# design.net
KiCad netlist of a schematic drawn in Altium Designer
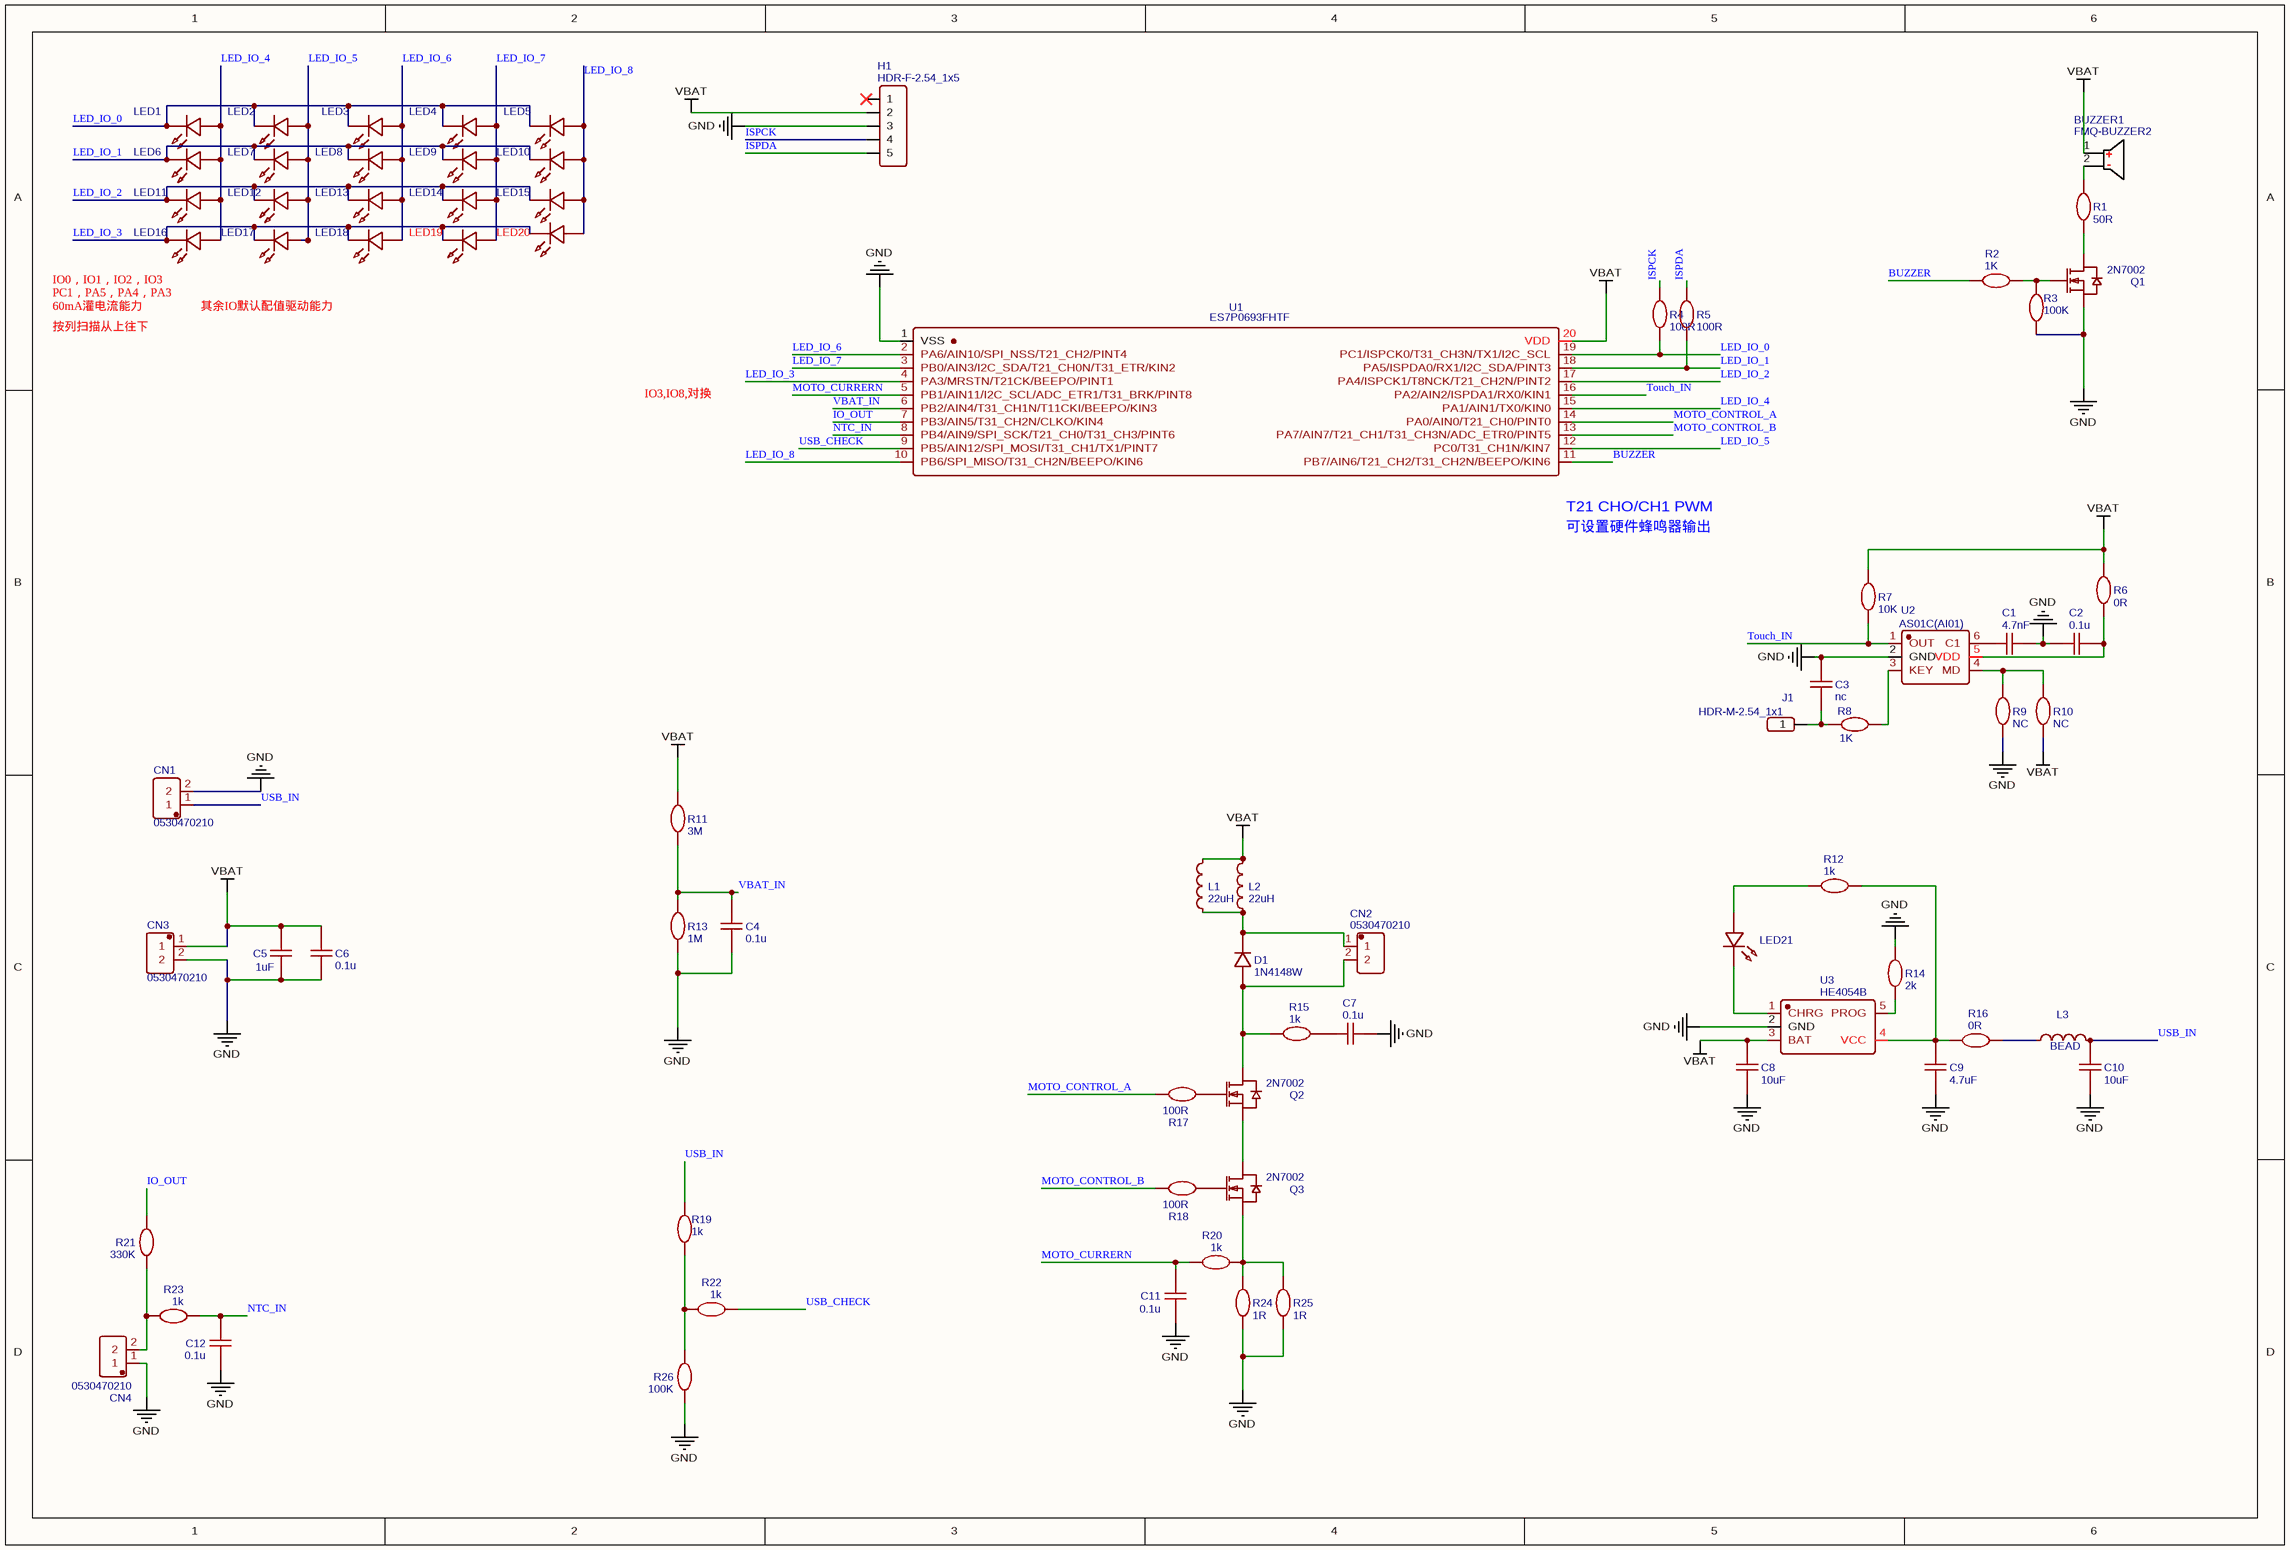
[diagram p0: 搅拌杯原理图.schdoc]

(export (version "E")
  (design (tool "Eeschema 10.0.6"))
  (components
    (comp (ref "BUZZER1")
      (value "FMQ-BUZZER2")
      (footprint "BUZ-TH_BD12.0-P7.60-D0.6-FD")
      (fields (field (name "BOM_SUPPLIER PART") "C9900006103") (field (name "CONTRIBUTOR") "LCSC"))
      (libsource (lib "altium-import") (part "root_0_FMQ-BUZZER2_"))
    )
    (comp (ref "C1")
      (value "4.7nF")
      (footprint "C0603")
      (fields (field (name "CONTRIBUTOR") "LCEDA_Lib"))
      (libsource (lib "altium-import") (part "root_0_4.7nF_"))
    )
    (comp (ref "C2")
      (value "0.1u")
      (footprint "C0603")
      (fields (field (name "CONTRIBUTOR") "LCEDA_Lib"))
      (libsource (lib "altium-import") (part "root_0_0.1u_"))
    )
    (comp (ref "C3")
      (value "nc")
      (footprint "C0603")
      (fields (field (name "CONTRIBUTOR") "LCEDA_Lib"))
      (libsource (lib "altium-import") (part "root_1_nc_"))
    )
    (comp (ref "C4")
      (value "0.1u")
      (footprint "C0603")
      (fields (field (name "CONTRIBUTOR") "LCEDA_Lib"))
      (libsource (lib "altium-import") (part "root_1_0.1u_"))
    )
    (comp (ref "C5")
      (value "1uF")
      (footprint "C0603")
      (fields (field (name "CONTRIBUTOR") "LCEDA_Lib"))
      (libsource (lib "altium-import") (part "root_3_1uF_"))
    )
    (comp (ref "C6")
      (value "0.1u")
      (footprint "C0603")
      (fields (field (name "CONTRIBUTOR") "LCEDA_Lib"))
      (libsource (lib "altium-import") (part "root_3_0.1u_"))
    )
    (comp (ref "C7")
      (value "0.1u")
      (footprint "C0603")
      (fields (field (name "CONTRIBUTOR") "LCEDA_Lib"))
      (libsource (lib "altium-import") (part "root_2_0.1u_"))
    )
    (comp (ref "C8")
      (value "10uF")
      (footprint "C0603")
      (fields (field (name "CONTRIBUTOR") "LCEDA_Lib"))
      (libsource (lib "altium-import") (part "root_1_10uF_"))
    )
    (comp (ref "C9")
      (value "4.7uF")
      (footprint "C0603")
      (fields (field (name "CONTRIBUTOR") "LCEDA_Lib"))
      (libsource (lib "altium-import") (part "root_1_4.7uF_"))
    )
    (comp (ref "C10")
      (value "10uF")
      (footprint "C0603")
      (fields (field (name "CONTRIBUTOR") "LCEDA_Lib"))
      (libsource (lib "altium-import") (part "root_1_10uF_"))
    )
    (comp (ref "C11")
      (value "0.1u")
      (footprint "C0603")
      (fields (field (name "CONTRIBUTOR") "LCEDA_Lib"))
      (libsource (lib "") (part "root_1_0.1u__1"))
    )
    (comp (ref "C12")
      (value "0.1u")
      (footprint "C0603")
      (fields (field (name "CONTRIBUTOR") "LCEDA_Lib"))
      (libsource (lib "") (part "root_3_0.1u__1"))
    )
    (comp (ref "CN1")
      (value "0530470210")
      (footprint "CONN-TH_0530470210")
      (fields (field (name "BOM_SUPPLIER PART") "C114130") (field (name "CONTRIBUTOR") "LCSC"))
      (libsource (lib "") (part "root_0_mirrored_0530470210__1"))
    )
    (comp (ref "CN2")
      (value "0530470210")
      (footprint "CONN-TH_0530470210")
      (fields (field (name "BOM_SUPPLIER PART") "C114130") (field (name "CONTRIBUTOR") "LCSC"))
      (libsource (lib "altium-import") (part "root_0_0530470210_"))
    )
    (comp (ref "CN3")
      (value "0530470210")
      (footprint "CONN-TH_0530470210")
      (fields (field (name "BOM_SUPPLIER PART") "C114130") (field (name "CONTRIBUTOR") "LCSC"))
      (libsource (lib "altium-import") (part "root_0_mirrored_0530470210_"))
    )
    (comp (ref "CN4")
      (value "0530470210")
      (footprint "CONN-TH_0530470210")
      (fields (field (name "BOM_SUPPLIER PART") "C114130") (field (name "CONTRIBUTOR") "LCSC"))
      (libsource (lib "") (part "root_0_0530470210__1"))
    )
    (comp (ref "D1")
      (value "1N4148W")
      (footprint "SOD-123FL_L2.6-W1.6-LS3.4-RD")
      (fields (field (name "BOM_SUPPLIER PART") "C129216") (field (name "CONTRIBUTOR") "LCEDA_Lib"))
      (libsource (lib "altium-import") (part "root_1_1N4148W_"))
    )
    (comp (ref "H1")
      (value "HDR-F-2.54_1x5")
      (footprint "1.27mm_5PIN")
      (fields (field (name "BOM_SUPPLIER PART") "C50950") (field (name "CONTRIBUTOR") "LCEDA_Lib"))
      (libsource (lib "altium-import") (part "root_0_HDR-F-2.54_1x5_"))
    )
    (comp (ref "J1")
      (value "HDR-M-2.54_1x1")
      (footprint "HDR-M-2.54_1X1")
      (fields (field (name "BOM_SUPPLIER PART") "C81276") (field (name "CONTRIBUTOR") "LCEDA_Lib"))
      (libsource (lib "altium-import") (part "root_2_HDR-M-2.54_1x1_"))
    )
    (comp (ref "L1")
      (value "22uH")
      (footprint "L0603")
      (fields (field (name "CONTRIBUTOR") "LCEDA_Lib"))
      (libsource (lib "altium-import") (part "root_1_22uH_"))
    )
    (comp (ref "L2")
      (value "22uH")
      (footprint "L0603")
      (fields (field (name "CONTRIBUTOR") "LCEDA_Lib"))
      (libsource (lib "altium-import") (part "root_1_22uH_"))
    )
    (comp (ref "L3")
      (value "BEAD")
      (footprint "L0603")
      (fields (field (name "CONTRIBUTOR") "LCEDA_Lib"))
      (libsource (lib "altium-import") (part "root_0_22uH_"))
    )
    (comp (ref "LED1")
      (value "LED-0603_W")
      (footprint "LED0603-FD_WHITE")
      (fields
        (field (name "BOM_MANUFACTURER PART") "17-21SURC/S530-A3/TR8")
        (field (name "BOM_SUPPLIER PART") "C72037")
        (field (name "CONTRIBUTOR") "LCEDA_Lib")
      )
      (libsource (lib "altium-import") (part "root_2_LED-0603_W_"))
    )
    (comp (ref "LED2")
      (value "LED-0603_W")
      (footprint "LED0603-FD_WHITE")
      (fields
        (field (name "BOM_MANUFACTURER PART") "17-21SURC/S530-A3/TR8")
        (field (name "BOM_SUPPLIER PART") "C72037")
        (field (name "CONTRIBUTOR") "LCEDA_Lib")
      )
      (libsource (lib "altium-import") (part "root_2_LED-0603_W_"))
    )
    (comp (ref "LED3")
      (value "LED-0603_W")
      (footprint "LED0603-FD_WHITE")
      (fields
        (field (name "BOM_MANUFACTURER PART") "17-21SURC/S530-A3/TR8")
        (field (name "BOM_SUPPLIER PART") "C72037")
        (field (name "CONTRIBUTOR") "LCEDA_Lib")
      )
      (libsource (lib "altium-import") (part "root_2_LED-0603_W_"))
    )
    (comp (ref "LED4")
      (value "LED-0603_W")
      (footprint "LED0603-FD_WHITE")
      (fields
        (field (name "BOM_MANUFACTURER PART") "17-21SURC/S530-A3/TR8")
        (field (name "BOM_SUPPLIER PART") "C72037")
        (field (name "CONTRIBUTOR") "LCEDA_Lib")
      )
      (libsource (lib "altium-import") (part "root_2_LED-0603_W_"))
    )
    (comp (ref "LED5")
      (value "LED-0603_W")
      (footprint "LED0603-FD_WHITE")
      (fields
        (field (name "BOM_MANUFACTURER PART") "17-21SURC/S530-A3/TR8")
        (field (name "BOM_SUPPLIER PART") "C72037")
        (field (name "CONTRIBUTOR") "LCEDA_Lib")
      )
      (libsource (lib "altium-import") (part "root_2_LED-0603_W_"))
    )
    (comp (ref "LED6")
      (value "LED-0603_W")
      (footprint "LED0603-FD_WHITE")
      (fields
        (field (name "BOM_MANUFACTURER PART") "17-21SURC/S530-A3/TR8")
        (field (name "BOM_SUPPLIER PART") "C72037")
        (field (name "CONTRIBUTOR") "LCEDA_Lib")
      )
      (libsource (lib "altium-import") (part "root_2_LED-0603_W_"))
    )
    (comp (ref "LED7")
      (value "LED-0603_W")
      (footprint "LED0603-FD_WHITE")
      (fields
        (field (name "BOM_MANUFACTURER PART") "17-21SURC/S530-A3/TR8")
        (field (name "BOM_SUPPLIER PART") "C72037")
        (field (name "CONTRIBUTOR") "LCEDA_Lib")
      )
      (libsource (lib "altium-import") (part "root_2_LED-0603_W_"))
    )
    (comp (ref "LED8")
      (value "LED-0603_W")
      (footprint "LED0603-FD_WHITE")
      (fields
        (field (name "BOM_MANUFACTURER PART") "17-21SURC/S530-A3/TR8")
        (field (name "BOM_SUPPLIER PART") "C72037")
        (field (name "CONTRIBUTOR") "LCEDA_Lib")
      )
      (libsource (lib "altium-import") (part "root_2_LED-0603_W_"))
    )
    (comp (ref "LED9")
      (value "LED-0603_W")
      (footprint "LED0603-FD_WHITE")
      (fields
        (field (name "BOM_MANUFACTURER PART") "17-21SURC/S530-A3/TR8")
        (field (name "BOM_SUPPLIER PART") "C72037")
        (field (name "CONTRIBUTOR") "LCEDA_Lib")
      )
      (libsource (lib "altium-import") (part "root_2_LED-0603_W_"))
    )
    (comp (ref "LED10")
      (value "LED-0603_W")
      (footprint "LED0603-FD_WHITE")
      (fields
        (field (name "BOM_MANUFACTURER PART") "17-21SURC/S530-A3/TR8")
        (field (name "BOM_SUPPLIER PART") "C72037")
        (field (name "CONTRIBUTOR") "LCEDA_Lib")
      )
      (libsource (lib "altium-import") (part "root_2_LED-0603_W_"))
    )
    (comp (ref "LED11")
      (value "LED-0603_W")
      (footprint "LED0603-FD_WHITE")
      (fields
        (field (name "BOM_MANUFACTURER PART") "17-21SURC/S530-A3/TR8")
        (field (name "BOM_SUPPLIER PART") "C72037")
        (field (name "CONTRIBUTOR") "LCEDA_Lib")
      )
      (libsource (lib "altium-import") (part "root_2_LED-0603_W_"))
    )
    (comp (ref "LED12")
      (value "LED-0603_W")
      (footprint "LED0603-FD_WHITE")
      (fields
        (field (name "BOM_MANUFACTURER PART") "17-21SURC/S530-A3/TR8")
        (field (name "BOM_SUPPLIER PART") "C72037")
        (field (name "CONTRIBUTOR") "LCEDA_Lib")
      )
      (libsource (lib "altium-import") (part "root_2_LED-0603_W_"))
    )
    (comp (ref "LED13")
      (value "LED-0603_W")
      (footprint "LED0603-FD_WHITE")
      (fields
        (field (name "BOM_MANUFACTURER PART") "17-21SURC/S530-A3/TR8")
        (field (name "BOM_SUPPLIER PART") "C72037")
        (field (name "CONTRIBUTOR") "LCEDA_Lib")
      )
      (libsource (lib "altium-import") (part "root_2_LED-0603_W_"))
    )
    (comp (ref "LED14")
      (value "LED-0603_W")
      (footprint "LED0603-FD_WHITE")
      (fields
        (field (name "BOM_MANUFACTURER PART") "17-21SURC/S530-A3/TR8")
        (field (name "BOM_SUPPLIER PART") "C72037")
        (field (name "CONTRIBUTOR") "LCEDA_Lib")
      )
      (libsource (lib "altium-import") (part "root_2_LED-0603_W_"))
    )
    (comp (ref "LED15")
      (value "LED-0603_W")
      (footprint "LED0603-FD_WHITE")
      (fields
        (field (name "BOM_MANUFACTURER PART") "17-21SURC/S530-A3/TR8")
        (field (name "BOM_SUPPLIER PART") "C72037")
        (field (name "CONTRIBUTOR") "LCEDA_Lib")
      )
      (libsource (lib "altium-import") (part "root_2_LED-0603_W_"))
    )
    (comp (ref "LED16")
      (value "LED-0603_W")
      (footprint "LED0603-FD_WHITE")
      (fields
        (field (name "BOM_MANUFACTURER PART") "17-21SURC/S530-A3/TR8")
        (field (name "BOM_SUPPLIER PART") "C72037")
        (field (name "CONTRIBUTOR") "LCEDA_Lib")
      )
      (libsource (lib "altium-import") (part "root_2_LED-0603_W_"))
    )
    (comp (ref "LED17")
      (value "LED-0603_W")
      (footprint "LED0603-FD_WHITE")
      (fields
        (field (name "BOM_MANUFACTURER PART") "17-21SURC/S530-A3/TR8")
        (field (name "BOM_SUPPLIER PART") "C72037")
        (field (name "CONTRIBUTOR") "LCEDA_Lib")
      )
      (libsource (lib "altium-import") (part "root_2_LED-0603_W_"))
    )
    (comp (ref "LED18")
      (value "LED-0603_W")
      (footprint "LED0603-FD_WHITE")
      (fields
        (field (name "BOM_MANUFACTURER PART") "17-21SURC/S530-A3/TR8")
        (field (name "BOM_SUPPLIER PART") "C72037")
        (field (name "CONTRIBUTOR") "LCEDA_Lib")
      )
      (libsource (lib "altium-import") (part "root_2_LED-0603_W_"))
    )
    (comp (ref "LED19")
      (value "LED-0603_W")
      (footprint "LED0603-FD_WHITE")
      (fields
        (field (name "BOM_MANUFACTURER PART") "17-21SURC/S530-A3/TR8")
        (field (name "BOM_SUPPLIER PART") "C72037")
        (field (name "CONTRIBUTOR") "LCEDA_Lib")
      )
      (libsource (lib "altium-import") (part "root_2_LED-0603_W_"))
    )
    (comp (ref "LED20")
      (value "LED-0603_W")
      (footprint "LED0603-FD_WHITE")
      (fields
        (field (name "BOM_MANUFACTURER PART") "17-21SURC/S530-A3/TR8")
        (field (name "BOM_SUPPLIER PART") "C72037")
        (field (name "CONTRIBUTOR") "LCEDA_Lib")
      )
      (libsource (lib "altium-import") (part "root_2_LED-0603_W_"))
    )
    (comp (ref "LED21")
      (value "LED-0603_W")
      (footprint "LED0603-FD_WHITE")
      (fields
        (field (name "BOM_MANUFACTURER PART") "17-21SURC/S530-A3/TR8")
        (field (name "BOM_SUPPLIER PART") "C72037")
        (field (name "CONTRIBUTOR") "LCEDA_Lib")
      )
      (libsource (lib "altium-import") (part "root_3_LED-0603_W_"))
    )
    (comp (ref "Q1")
      (value "2N7002")
      (footprint "SOT-23_L2.9-W1.3-P0.95-LS2.4-BR")
      (fields
        (field (name "BOM_MANUFACTURER PART") "2N7002,215")
        (field (name "BOM_SUPPLIER PART") "C65189")
        (field (name "CONTRIBUTOR") "LCEDA_Lib")
      )
      (libsource (lib "altium-import") (part "root_2_2N7002_"))
    )
    (comp (ref "Q2")
      (value "2N7002")
      (footprint "SOT-23_L2.9-W1.3-P0.95-LS2.4-BR")
      (fields
        (field (name "BOM_MANUFACTURER PART") "2N7002,215")
        (field (name "BOM_SUPPLIER PART") "C65189")
        (field (name "CONTRIBUTOR") "LCEDA_Lib")
      )
      (libsource (lib "altium-import") (part "root_2_2N7002_"))
    )
    (comp (ref "Q3")
      (value "2N7002")
      (footprint "SOT-23_L2.9-W1.3-P0.95-LS2.4-BR")
      (fields
        (field (name "BOM_MANUFACTURER PART") "2N7002,215")
        (field (name "BOM_SUPPLIER PART") "C65189")
        (field (name "CONTRIBUTOR") "LCEDA_Lib")
      )
      (libsource (lib "altium-import") (part "root_2_2N7002_"))
    )
    (comp (ref "R1")
      (value "50R")
      (footprint "R0603")
      (fields (field (name "CONTRIBUTOR") "LCEDA_Lib"))
      (libsource (lib "altium-import") (part "root_3_100R_"))
    )
    (comp (ref "R2")
      (value "1K")
      (footprint "R0603")
      (fields (field (name "CONTRIBUTOR") "LCEDA_Lib"))
      (libsource (lib "altium-import") (part "root_2_1K_"))
    )
    (comp (ref "R3")
      (value "100K")
      (footprint "R0603")
      (fields (field (name "CONTRIBUTOR") "LCEDA_Lib"))
      (libsource (lib "altium-import") (part "root_3_1K_"))
    )
    (comp (ref "R4")
      (value "100R")
      (footprint "R0603")
      (fields (field (name "CONTRIBUTOR") "LCEDA_Lib"))
      (libsource (lib "altium-import") (part "root_3_100R_"))
    )
    (comp (ref "R5")
      (value "100R")
      (footprint "R0603")
      (fields (field (name "CONTRIBUTOR") "LCEDA_Lib"))
      (libsource (lib "altium-import") (part "root_3_100R_"))
    )
    (comp (ref "R6")
      (value "0R")
      (footprint "R0603")
      (fields (field (name "CONTRIBUTOR") "LCEDA_Lib"))
      (libsource (lib "altium-import") (part "root_1_NC_"))
    )
    (comp (ref "R7")
      (value "10K")
      (footprint "R0603")
      (fields (field (name "CONTRIBUTOR") "LCEDA_Lib"))
      (libsource (lib "altium-import") (part "root_1_NC_"))
    )
    (comp (ref "R8")
      (value "1K")
      (footprint "R0603")
      (fields (field (name "CONTRIBUTOR") "LCEDA_Lib"))
      (libsource (lib "altium-import") (part "root_2_1K_"))
    )
    (comp (ref "R9")
      (value "NC")
      (footprint "R0603")
      (fields (field (name "CONTRIBUTOR") "LCEDA_Lib"))
      (libsource (lib "altium-import") (part "root_1_NC_"))
    )
    (comp (ref "R10")
      (value "NC")
      (footprint "R0603")
      (fields (field (name "CONTRIBUTOR") "LCEDA_Lib"))
      (libsource (lib "altium-import") (part "root_1_NC_"))
    )
    (comp (ref "R11")
      (value "3M")
      (footprint "R0603")
      (fields (field (name "CONTRIBUTOR") "LCEDA_Lib"))
      (libsource (lib "altium-import") (part "root_1_430k_"))
    )
    (comp (ref "R12")
      (value "1k")
      (footprint "R0603")
      (fields (field (name "CONTRIBUTOR") "LCEDA_Lib"))
      (libsource (lib "") (part "root_2_1k__1"))
    )
    (comp (ref "R13")
      (value "1M")
      (footprint "R0603")
      (fields (field (name "CONTRIBUTOR") "LCEDA_Lib"))
      (libsource (lib "altium-import") (part "root_1_430K_"))
    )
    (comp (ref "R14")
      (value "2k")
      (footprint "R0603")
      (fields (field (name "CONTRIBUTOR") "LCEDA_Lib"))
      (libsource (lib "altium-import") (part "root_1_1k_"))
    )
    (comp (ref "R15")
      (value "1k")
      (footprint "R0603")
      (fields (field (name "CONTRIBUTOR") "LCEDA_Lib"))
      (libsource (lib "") (part "root_2_1k__1"))
    )
    (comp (ref "R16")
      (value "0R")
      (footprint "R0603")
      (fields (field (name "CONTRIBUTOR") "LCEDA_Lib"))
      (libsource (lib "altium-import") (part "root_0_NC_"))
    )
    (comp (ref "R17")
      (value "100R")
      (footprint "R0603")
      (fields (field (name "CONTRIBUTOR") "LCEDA_Lib"))
      (libsource (lib "altium-import") (part "root_2_100R_"))
    )
    (comp (ref "R18")
      (value "100R")
      (footprint "R0603")
      (fields (field (name "CONTRIBUTOR") "LCEDA_Lib"))
      (libsource (lib "altium-import") (part "root_2_100R_"))
    )
    (comp (ref "R19")
      (value "1k")
      (footprint "R0603")
      (fields (field (name "CONTRIBUTOR") "LCEDA_Lib"))
      (libsource (lib "altium-import") (part "root_3_1k_"))
    )
    (comp (ref "R20")
      (value "1k")
      (footprint "R0603")
      (fields (field (name "CONTRIBUTOR") "LCEDA_Lib"))
      (libsource (lib "altium-import") (part "root_0_1k_"))
    )
    (comp (ref "R21")
      (value "330K")
      (footprint "R0603")
      (fields (field (name "CONTRIBUTOR") "LCEDA_Lib"))
      (libsource (lib "altium-import") (part "root_3_33K_"))
    )
    (comp (ref "R22")
      (value "1k")
      (footprint "R0603")
      (fields (field (name "CONTRIBUTOR") "LCEDA_Lib"))
      (libsource (lib "altium-import") (part "root_2_1k_"))
    )
    (comp (ref "R23")
      (value "1k")
      (footprint "R0603")
      (fields (field (name "CONTRIBUTOR") "LCEDA_Lib"))
      (libsource (lib "altium-import") (part "root_2_1k_"))
    )
    (comp (ref "R24")
      (value "1R")
      (footprint "R1206")
      (fields (field (name "CONTRIBUTOR") "LCEDA_Lib"))
      (libsource (lib "altium-import") (part "root_1_1R_"))
    )
    (comp (ref "R25")
      (value "1R")
      (footprint "R1206")
      (fields (field (name "CONTRIBUTOR") "LCEDA_Lib"))
      (libsource (lib "altium-import") (part "root_1_1R_"))
    )
    (comp (ref "R26")
      (value "100K")
      (footprint "R0603")
      (fields (field (name "CONTRIBUTOR") "LCEDA_Lib"))
      (libsource (lib "altium-import") (part "root_3_33K_"))
    )
    (comp (ref "U1")
      (value "ES7P0693FHTF")
      (footprint "TSOP20")
      (fields (field (name "CONTRIBUTOR") "zime_zl"))
      (libsource (lib "altium-import") (part "root_0_ES7P0693FHTF_"))
    )
    (comp (ref "U2")
      (value "AS01C(AI01)")
      (footprint "SOT-23-6_L2.9-W1.6-P0.95-LS2.8-BL")
      (fields (field (name "BOM_SUPPLIER PART") "C389617") (field (name "CONTRIBUTOR") "LCSC"))
      (libsource (lib "altium-import") (part "root_0_AS01C(AI01)_"))
    )
    (comp (ref "U3")
      (value "HE4054B")
      (footprint "SOT-23-5_L3.0-W1.7-P0.95-LS2.8-BR")
      (fields (field (name "BOM_SUPPLIER PART") "C711953") (field (name "CONTRIBUTOR") "LCSC"))
      (libsource (lib "altium-import") (part "root_0_HE4054B_"))
    )
  )
  (nets
    (net (code "1") (name "/BUZZER") (class "Default")
      (node (ref "R2") (pin "2") (pinfunction "2_2") (pintype "passive"))
      (node (ref "U1") (pin "11") (pinfunction "PB7/AIN6/T21_CH2/T31_CH2N/BEEPO/KIN6_11") (pintype "passive"))
    )
    (net (code "2") (name "/IO_OUT") (class "Default")
      (node (ref "R21") (pin "1") (pinfunction "1_1") (pintype "passive"))
      (node (ref "U1") (pin "7") (pinfunction "PB3/AIN5/T31_CH2N/CLKO/KIN4_7") (pintype "passive"))
    )
    (net (code "3") (name "/ISPCK") (class "Default")
      (node (ref "H1") (pin "4") (pinfunction "4_4") (pintype "passive"))
      (node (ref "R4") (pin "1") (pinfunction "1_1") (pintype "passive"))
    )
    (net (code "4") (name "/ISPDA") (class "Default")
      (node (ref "H1") (pin "5") (pinfunction "5_5") (pintype "passive"))
      (node (ref "R5") (pin "1") (pinfunction "1_1") (pintype "passive"))
    )
    (net (code "5") (name "/LED_IO_0") (class "Default")
      (node (ref "LED1") (pin "2") (pinfunction "2_2") (pintype "passive"))
      (node (ref "LED2") (pin "2") (pinfunction "2_2") (pintype "passive"))
      (node (ref "LED3") (pin "2") (pinfunction "2_2") (pintype "passive"))
      (node (ref "LED4") (pin "2") (pinfunction "2_2") (pintype "passive"))
      (node (ref "LED5") (pin "2") (pinfunction "2_2") (pintype "passive"))
      (node (ref "R4") (pin "2") (pinfunction "2_2") (pintype "passive"))
      (node (ref "U1") (pin "19") (pinfunction "PC1/ISPCK0/T31_CH3N/TX1/I2C_SCL_19") (pintype "passive"))
    )
    (net (code "6") (name "/LED_IO_1") (class "Default")
      (node (ref "LED10") (pin "2") (pinfunction "2_2") (pintype "passive"))
      (node (ref "LED6") (pin "2") (pinfunction "2_2") (pintype "passive"))
      (node (ref "LED7") (pin "2") (pinfunction "2_2") (pintype "passive"))
      (node (ref "LED8") (pin "2") (pinfunction "2_2") (pintype "passive"))
      (node (ref "LED9") (pin "2") (pinfunction "2_2") (pintype "passive"))
      (node (ref "R5") (pin "2") (pinfunction "2_2") (pintype "passive"))
      (node (ref "U1") (pin "18") (pinfunction "PA5/ISPDA0/RX1/I2C_SDA/PINT3_18") (pintype "passive"))
    )
    (net (code "7") (name "/LED_IO_2") (class "Default")
      (node (ref "LED11") (pin "2") (pinfunction "2_2") (pintype "passive"))
      (node (ref "LED12") (pin "2") (pinfunction "2_2") (pintype "passive"))
      (node (ref "LED13") (pin "2") (pinfunction "2_2") (pintype "passive"))
      (node (ref "LED14") (pin "2") (pinfunction "2_2") (pintype "passive"))
      (node (ref "LED15") (pin "2") (pinfunction "2_2") (pintype "passive"))
      (node (ref "U1") (pin "17") (pinfunction "PA4/ISPCK1/T8NCK/T21_CH2N/PINT2_17") (pintype "passive"))
    )
    (net (code "8") (name "/LED_IO_3") (class "Default")
      (node (ref "LED16") (pin "2") (pinfunction "2_2") (pintype "passive"))
      (node (ref "LED17") (pin "2") (pinfunction "2_2") (pintype "passive"))
      (node (ref "LED18") (pin "2") (pinfunction "2_2") (pintype "passive"))
      (node (ref "LED19") (pin "2") (pinfunction "2_2") (pintype "passive"))
      (node (ref "LED20") (pin "2") (pinfunction "2_2") (pintype "passive"))
      (node (ref "U1") (pin "4") (pinfunction "PA3/MRSTN/T21CK/BEEPO/PINT1_4") (pintype "passive"))
    )
    (net (code "9") (name "/LED_IO_4") (class "Default")
      (node (ref "LED1") (pin "1") (pinfunction "1_1") (pintype "passive"))
      (node (ref "LED11") (pin "1") (pinfunction "1_1") (pintype "passive"))
      (node (ref "LED16") (pin "1") (pinfunction "1_1") (pintype "passive"))
      (node (ref "LED6") (pin "1") (pinfunction "1_1") (pintype "passive"))
      (node (ref "U1") (pin "15") (pinfunction "PA1/AIN1/TX0/KIN0_15") (pintype "passive"))
    )
    (net (code "10") (name "/LED_IO_5") (class "Default")
      (node (ref "LED12") (pin "1") (pinfunction "1_1") (pintype "passive"))
      (node (ref "LED17") (pin "1") (pinfunction "1_1") (pintype "passive"))
      (node (ref "LED2") (pin "1") (pinfunction "1_1") (pintype "passive"))
      (node (ref "LED7") (pin "1") (pinfunction "1_1") (pintype "passive"))
      (node (ref "U1") (pin "12") (pinfunction "PC0/T31_CH1N/KIN7_12") (pintype "passive"))
    )
    (net (code "11") (name "/LED_IO_6") (class "Default")
      (node (ref "LED13") (pin "1") (pinfunction "1_1") (pintype "passive"))
      (node (ref "LED18") (pin "1") (pinfunction "1_1") (pintype "passive"))
      (node (ref "LED3") (pin "1") (pinfunction "1_1") (pintype "passive"))
      (node (ref "LED8") (pin "1") (pinfunction "1_1") (pintype "passive"))
      (node (ref "U1") (pin "2") (pinfunction "PA6/AIN10/SPI_NSS/T21_CH2/PINT4_2") (pintype "passive"))
    )
    (net (code "12") (name "/LED_IO_7") (class "Default")
      (node (ref "LED14") (pin "1") (pinfunction "1_1") (pintype "passive"))
      (node (ref "LED19") (pin "1") (pinfunction "1_1") (pintype "passive"))
      (node (ref "LED4") (pin "1") (pinfunction "1_1") (pintype "passive"))
      (node (ref "LED9") (pin "1") (pinfunction "1_1") (pintype "passive"))
      (node (ref "U1") (pin "3") (pinfunction "PB0/AIN3/I2C_SDA/T21_CH0N/T31_ETR/KIN2_3") (pintype "passive"))
    )
    (net (code "13") (name "/LED_IO_8") (class "Default")
      (node (ref "LED10") (pin "1") (pinfunction "1_1") (pintype "passive"))
      (node (ref "LED15") (pin "1") (pinfunction "1_1") (pintype "passive"))
      (node (ref "LED20") (pin "1") (pinfunction "1_1") (pintype "passive"))
      (node (ref "LED5") (pin "1") (pinfunction "1_1") (pintype "passive"))
      (node (ref "U1") (pin "10") (pinfunction "PB6/SPI_MISO/T31_CH2N/BEEPO/KIN6_10") (pintype "passive"))
    )
    (net (code "14") (name "/MOTO_CONTROL_A") (class "Default")
      (node (ref "R17") (pin "1") (pinfunction "1_1") (pintype "passive"))
      (node (ref "U1") (pin "14") (pinfunction "PA0/AIN0/T21_CH0/PINT0_14") (pintype "passive"))
    )
    (net (code "15") (name "/MOTO_CONTROL_B") (class "Default")
      (node (ref "R18") (pin "1") (pinfunction "1_1") (pintype "passive"))
      (node (ref "U1") (pin "13") (pinfunction "PA7/AIN7/T21_CH1/T31_CH3N/ADC_ETR0/PINT5_13") (pintype "passive"))
    )
    (net (code "16") (name "/MOTO_CURRERN") (class "Default")
      (node (ref "C11") (pin "2") (pinfunction "2_2") (pintype "passive"))
      (node (ref "R20") (pin "2") (pinfunction "2_2") (pintype "passive"))
      (node (ref "U1") (pin "5") (pinfunction "PB1/AIN11/I2C_SCL/ADC_ETR1/T31_BRK/PINT8_5") (pintype "passive"))
    )
    (net (code "17") (name "/NTC_IN") (class "Default")
      (node (ref "C12") (pin "1") (pinfunction "1_1") (pintype "passive"))
      (node (ref "R23") (pin "2") (pinfunction "2_2") (pintype "passive"))
      (node (ref "U1") (pin "8") (pinfunction "PB4/AIN9/SPI_SCK/T21_CH0/T31_CH3/PINT6_8") (pintype "passive"))
    )
    (net (code "18") (name "/Touch_IN") (class "Default")
      (node (ref "R7") (pin "1") (pinfunction "1_1") (pintype "passive"))
      (node (ref "U1") (pin "16") (pinfunction "PA2/AIN2/ISPDA1/RX0/KIN1_16") (pintype "passive"))
      (node (ref "U2") (pin "1") (pinfunction "OUT_1") (pintype "passive"))
    )
    (net (code "19") (name "/USB_CHECK") (class "Default")
      (node (ref "R22") (pin "2") (pinfunction "2_2") (pintype "passive"))
      (node (ref "U1") (pin "9") (pinfunction "PB5/AIN12/SPI_MOSI/T31_CH1/TX1/PINT7_9") (pintype "passive"))
    )
    (net (code "20") (name "/USB_IN") (class "Default")
      (node (ref "C10") (pin "2") (pinfunction "2_2") (pintype "passive"))
      (node (ref "CN1") (pin "1") (pinfunction "1_1") (pintype "passive"))
      (node (ref "L3") (pin "2") (pinfunction "2_2") (pintype "passive"))
      (node (ref "R19") (pin "2") (pinfunction "2_2") (pintype "passive"))
    )
    (net (code "21") (name "/VBAT_IN") (class "Default")
      (node (ref "C4") (pin "2") (pinfunction "2_2") (pintype "passive"))
      (node (ref "R11") (pin "1") (pinfunction "1_1") (pintype "passive"))
      (node (ref "R13") (pin "2") (pinfunction "2_2") (pintype "passive"))
      (node (ref "U1") (pin "6") (pinfunction "PB2/AIN4/T31_CH1N/T11CKI/BEEPO/KIN3_6") (pintype "passive"))
    )
    (net (code "22") (name "GND") (class "Default")
      (node (ref "C1") (pin "2") (pinfunction "2_2") (pintype "passive"))
      (node (ref "C10") (pin "1") (pinfunction "1_1") (pintype "passive"))
      (node (ref "C11") (pin "1") (pinfunction "1_1") (pintype "passive"))
      (node (ref "C12") (pin "2") (pinfunction "2_2") (pintype "passive"))
      (node (ref "C2") (pin "1") (pinfunction "1_1") (pintype "passive"))
      (node (ref "C3") (pin "2") (pinfunction "2_2") (pintype "passive"))
      (node (ref "C4") (pin "1") (pinfunction "1_1") (pintype "passive"))
      (node (ref "C5") (pin "2") (pinfunction "2_2") (pintype "passive"))
      (node (ref "C6") (pin "2") (pinfunction "2_2") (pintype "passive"))
      (node (ref "C7") (pin "1") (pinfunction "1_1") (pintype "passive"))
      (node (ref "C8") (pin "1") (pinfunction "1_1") (pintype "passive"))
      (node (ref "C9") (pin "1") (pinfunction "1_1") (pintype "passive"))
      (node (ref "CN1") (pin "2") (pinfunction "2_2") (pintype "passive"))
      (node (ref "CN3") (pin "2") (pinfunction "2_2") (pintype "passive"))
      (node (ref "CN4") (pin "1") (pinfunction "1_1") (pintype "passive"))
      (node (ref "H1") (pin "3") (pinfunction "3_3") (pintype "passive"))
      (node (ref "Q1") (pin "2") (pinfunction "S_2") (pintype "passive"))
      (node (ref "R13") (pin "1") (pinfunction "1_1") (pintype "passive"))
      (node (ref "R14") (pin "2") (pinfunction "2_2") (pintype "passive"))
      (node (ref "R24") (pin "1") (pinfunction "1_1") (pintype "passive"))
      (node (ref "R25") (pin "1") (pinfunction "1_1") (pintype "passive"))
      (node (ref "R26") (pin "2") (pinfunction "2_2") (pintype "passive"))
      (node (ref "R3") (pin "2") (pinfunction "2_2") (pintype "passive"))
      (node (ref "R9") (pin "1") (pinfunction "1_1") (pintype "passive"))
      (node (ref "U1") (pin "1") (pinfunction "VSS_1") (pintype "passive"))
      (node (ref "U2") (pin "2") (pinfunction "GND_2") (pintype "passive"))
      (node (ref "U3") (pin "2") (pinfunction "GND_2") (pintype "passive"))
    )
    (net (code "23") (name "Net-(BUZZER1-Pad2)") (class "Default")
      (node (ref "BUZZER1") (pin "2") (pinfunction "2_2") (pintype "passive"))
      (node (ref "R1") (pin "1") (pinfunction "1_1") (pintype "passive"))
    )
    (net (code "24") (name "Net-(C3-Pad1)") (class "Default")
      (node (ref "C3") (pin "1") (pinfunction "1_1") (pintype "passive"))
      (node (ref "J1") (pin "1") (pinfunction "1_1") (pintype "passive"))
      (node (ref "R8") (pin "2") (pinfunction "2_2") (pintype "passive"))
    )
    (net (code "25") (name "Net-(C7-Pad2)") (class "Default")
      (node (ref "C7") (pin "2") (pinfunction "2_2") (pintype "passive"))
      (node (ref "R15") (pin "1") (pinfunction "1_1") (pintype "passive"))
    )
    (net (code "26") (name "Net-(CN2-Pad1)") (class "Default")
      (node (ref "CN2") (pin "1") (pinfunction "1_1") (pintype "passive"))
      (node (ref "D1") (pin "1") (pinfunction "1_1") (pintype "passive"))
      (node (ref "L1") (pin "1") (pinfunction "1_1") (pintype "passive"))
      (node (ref "L2") (pin "1") (pinfunction "1_1") (pintype "passive"))
    )
    (net (code "27") (name "Net-(CN4-Pad2)") (class "Default")
      (node (ref "CN4") (pin "2") (pinfunction "2_2") (pintype "passive"))
      (node (ref "R21") (pin "2") (pinfunction "2_2") (pintype "passive"))
      (node (ref "R23") (pin "1") (pinfunction "1_1") (pintype "passive"))
    )
    (net (code "28") (name "Net-(L3-Pad1)") (class "Default")
      (node (ref "L3") (pin "1") (pinfunction "1_1") (pintype "passive"))
      (node (ref "R16") (pin "2") (pinfunction "2_2") (pintype "passive"))
    )
    (net (code "29") (name "Net-(LED21-Pad1)") (class "Default")
      (node (ref "LED21") (pin "1") (pinfunction "1_1") (pintype "passive"))
      (node (ref "R12") (pin "2") (pinfunction "2_2") (pintype "passive"))
    )
    (net (code "30") (name "Net-(Q1-D)") (class "Default")
      (node (ref "Q1") (pin "3") (pinfunction "D_3") (pintype "passive"))
      (node (ref "R1") (pin "2") (pinfunction "2_2") (pintype "passive"))
    )
    (net (code "31") (name "Net-(Q1-G)") (class "Default")
      (node (ref "Q1") (pin "1") (pinfunction "G_1") (pintype "passive"))
      (node (ref "R2") (pin "1") (pinfunction "1_1") (pintype "passive"))
      (node (ref "R3") (pin "1") (pinfunction "1_1") (pintype "passive"))
    )
    (net (code "32") (name "Net-(Q2-D)") (class "Default")
      (node (ref "CN2") (pin "2") (pinfunction "2_2") (pintype "passive"))
      (node (ref "D1") (pin "2") (pinfunction "2_2") (pintype "passive"))
      (node (ref "Q2") (pin "3") (pinfunction "D_3") (pintype "passive"))
      (node (ref "R15") (pin "2") (pinfunction "2_2") (pintype "passive"))
    )
    (net (code "33") (name "Net-(Q2-G)") (class "Default")
      (node (ref "Q2") (pin "1") (pinfunction "G_1") (pintype "passive"))
      (node (ref "R17") (pin "2") (pinfunction "2_2") (pintype "passive"))
    )
    (net (code "34") (name "Net-(Q2-S)") (class "Default")
      (node (ref "Q2") (pin "2") (pinfunction "S_2") (pintype "passive"))
      (node (ref "Q3") (pin "3") (pinfunction "D_3") (pintype "passive"))
    )
    (net (code "35") (name "Net-(Q3-G)") (class "Default")
      (node (ref "Q3") (pin "1") (pinfunction "G_1") (pintype "passive"))
      (node (ref "R18") (pin "2") (pinfunction "2_2") (pintype "passive"))
    )
    (net (code "36") (name "Net-(Q3-S)") (class "Default")
      (node (ref "Q3") (pin "2") (pinfunction "S_2") (pintype "passive"))
      (node (ref "R20") (pin "1") (pinfunction "1_1") (pintype "passive"))
      (node (ref "R24") (pin "2") (pinfunction "2_2") (pintype "passive"))
      (node (ref "R25") (pin "2") (pinfunction "2_2") (pintype "passive"))
    )
    (net (code "37") (name "Net-(R19-Pad1)") (class "Default")
      (node (ref "R19") (pin "1") (pinfunction "1_1") (pintype "passive"))
      (node (ref "R22") (pin "1") (pinfunction "1_1") (pintype "passive"))
      (node (ref "R26") (pin "1") (pinfunction "1_1") (pintype "passive"))
    )
    (net (code "38") (name "Net-(U2-C1)") (class "Default")
      (node (ref "C1") (pin "1") (pinfunction "1_1") (pintype "passive"))
      (node (ref "U2") (pin "6") (pinfunction "C1_6") (pintype "passive"))
    )
    (net (code "39") (name "Net-(U2-KEY)") (class "Default")
      (node (ref "R8") (pin "1") (pinfunction "1_1") (pintype "passive"))
      (node (ref "U2") (pin "3") (pinfunction "KEY_3") (pintype "passive"))
    )
    (net (code "40") (name "Net-(U2-MD)") (class "Default")
      (node (ref "R10") (pin "2") (pinfunction "2_2") (pintype "passive"))
      (node (ref "R9") (pin "2") (pinfunction "2_2") (pintype "passive"))
      (node (ref "U2") (pin "4") (pinfunction "MD_4") (pintype "passive"))
    )
    (net (code "41") (name "Net-(U2-VDD)") (class "Default")
      (node (ref "C2") (pin "2") (pinfunction "2_2") (pintype "passive"))
      (node (ref "R6") (pin "1") (pinfunction "1_1") (pintype "passive"))
      (node (ref "U2") (pin "5") (pinfunction "VDD_5") (pintype "passive"))
    )
    (net (code "42") (name "Net-(U3-CHRG)") (class "Default")
      (node (ref "LED21") (pin "2") (pinfunction "2_2") (pintype "passive"))
      (node (ref "U3") (pin "1") (pinfunction "CHRG_1") (pintype "passive"))
    )
    (net (code "43") (name "Net-(U3-PROG)") (class "Default")
      (node (ref "R14") (pin "1") (pinfunction "1_1") (pintype "passive"))
      (node (ref "U3") (pin "5") (pinfunction "PROG_5") (pintype "passive"))
    )
    (net (code "44") (name "Net-(U3-VCC)") (class "Default")
      (node (ref "C9") (pin "2") (pinfunction "2_2") (pintype "passive"))
      (node (ref "R12") (pin "1") (pinfunction "1_1") (pintype "passive"))
      (node (ref "R16") (pin "1") (pinfunction "1_1") (pintype "passive"))
      (node (ref "U3") (pin "4") (pinfunction "VCC_4") (pintype "passive"))
    )
    (net (code "45") (name "VBAT") (class "Default")
      (node (ref "BUZZER1") (pin "1") (pinfunction "1_1") (pintype "passive"))
      (node (ref "C5") (pin "1") (pinfunction "1_1") (pintype "passive"))
      (node (ref "C6") (pin "1") (pinfunction "1_1") (pintype "passive"))
      (node (ref "C8") (pin "2") (pinfunction "2_2") (pintype "passive"))
      (node (ref "CN3") (pin "1") (pinfunction "1_1") (pintype "passive"))
      (node (ref "H1") (pin "2") (pinfunction "2_2") (pintype "passive"))
      (node (ref "L1") (pin "2") (pinfunction "2_2") (pintype "passive"))
      (node (ref "L2") (pin "2") (pinfunction "2_2") (pintype "passive"))
      (node (ref "R10") (pin "1") (pinfunction "1_1") (pintype "passive"))
      (node (ref "R11") (pin "2") (pinfunction "2_2") (pintype "passive"))
      (node (ref "R6") (pin "2") (pinfunction "2_2") (pintype "passive"))
      (node (ref "R7") (pin "2") (pinfunction "2_2") (pintype "passive"))
      (node (ref "U1") (pin "20") (pinfunction "VDD_20") (pintype "passive"))
      (node (ref "U3") (pin "3") (pinfunction "BAT_3") (pintype "passive"))
    )
    (net (code "46") (name "unconnected-(H1-Pad1)") (class "Default")
      (node (ref "H1") (pin "1") (pinfunction "1_1") (pintype "passive+no_connect"))
    )
  )
)
